# Morpheus_MCU.net
KiCad netlist of a schematic drawn in Altium Designer
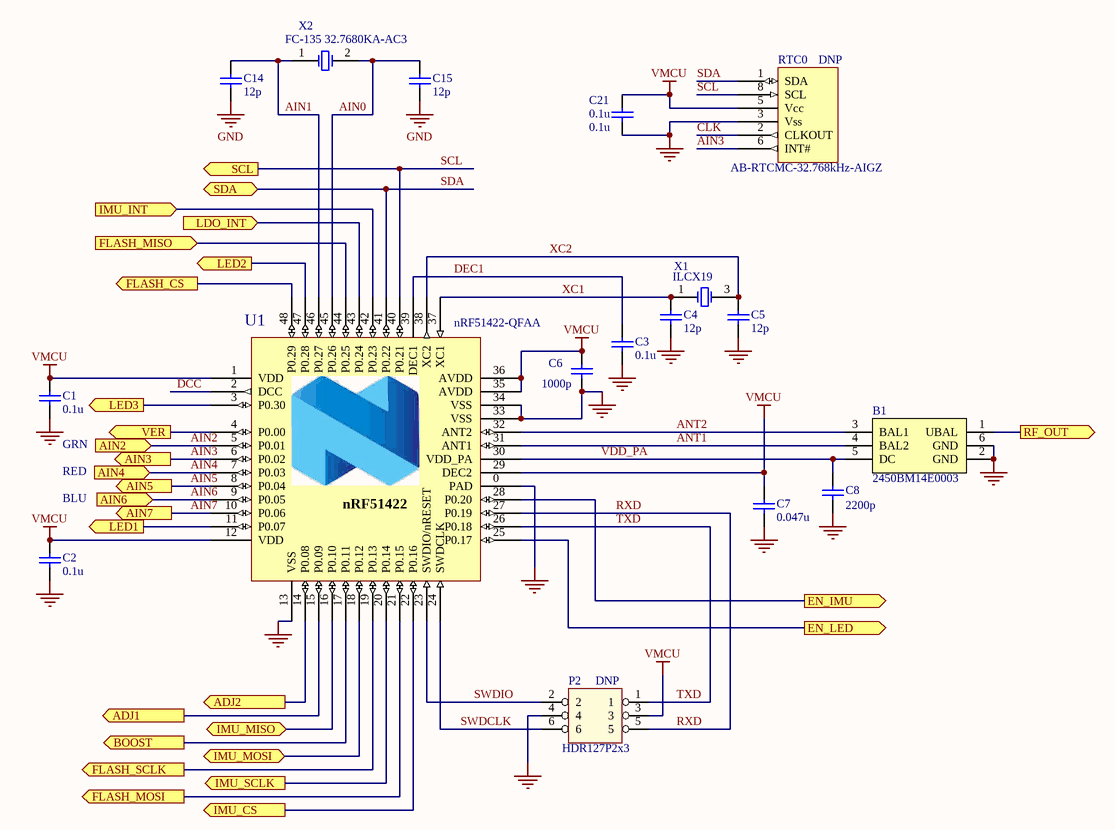
[diagram p0: Morpheus_MCU.SchDoc]

(export (version "E")
  (design (tool "Eeschema 10.0.6"))
  (components
    (comp (ref "B1")
      (value "2450BM14E0003")
      (footprint "DFN50P160X80X70-6N")
      (description "BALUN FILTER for NORDIC nRF51x22 QFN")
      (libsource (lib "Morpheus_pill") (part "2450BM14E0003"))
    )
    (comp (ref "C1")
      (value "0.1u")
      (footprint "CAP0402_SENSE_DVT")
      (description "CAP CER 0.1UF 50V 10% X7R 0402")
      (fields (field (name "TOLERANCE") "10%") (field (name "VOLTAGE") "50V"))
      (libsource (lib "Morpheus_pill") (part "C_0.1u_10_50_X7R_0402"))
    )
    (comp (ref "C2")
      (value "0.1u")
      (footprint "CAP0402_SENSE_DVT")
      (description "CAP CER 0.1UF 50V 10% X7R 0402")
      (fields (field (name "TOLERANCE") "10%") (field (name "VOLTAGE") "50V"))
      (libsource (lib "Morpheus_pill") (part "C_0.1u_10_50_X7R_0402"))
    )
    (comp (ref "C3")
      (value "0.1u")
      (footprint "CAP0402_SENSE_DVT")
      (description "CAP CER 0.1UF 50V 10% X7R 0402")
      (fields (field (name "TOLERANCE") "10%") (field (name "VOLTAGE") "50V"))
      (libsource (lib "Morpheus_pill") (part "C_0.1u_10_50_X7R_0402"))
    )
    (comp (ref "C4")
      (value "12p")
      (footprint "CAP0402_SENSE_DVT")
      (description "CAP CER 12PF 50V 5% NP0 0402")
      (fields (field (name "TOLERANCE") "5%") (field (name "VOLTAGE") "50V"))
      (libsource (lib "Morpheus_pill") (part "C_12p_5_50_C0G_0402"))
    )
    (comp (ref "C5")
      (value "12p")
      (footprint "CAP0402_SENSE_DVT")
      (description "CAP CER 12PF 50V 5% NP0 0402")
      (fields (field (name "TOLERANCE") "5%") (field (name "VOLTAGE") "50V"))
      (libsource (lib "Morpheus_pill") (part "C_12p_5_50_C0G_0402"))
    )
    (comp (ref "C6")
      (value "1000p")
      (footprint "CAP0201_SENSE_DVT")
      (description "CAP CER 1000PF 25V 10% X7R 0201")
      (fields (field (name "TOLERANCE") "10%") (field (name "VOLTAGE") "25V"))
      (libsource (lib "Morpheus_pill") (part "C_1000p_10_25_X7R_0201"))
    )
    (comp (ref "C7")
      (value "0.047u")
      (footprint "CAP0201_SENSE_DVT")
      (description "CAP CER 0.047UF 16V 10% X5R 0201")
      (fields (field (name "TOLERANCE") "10%") (field (name "VOLTAGE") "16V"))
      (libsource (lib "Morpheus_pill") (part "C_0.047u_10_16_X5R_0201"))
    )
    (comp (ref "C8")
      (value "2200p")
      (footprint "CAP0201_SENSE_DVT")
      (description "CAP CER 2200PF 16V 10% X7R 0201")
      (fields (field (name "TOLERANCE") "5 %") (field (name "VOLTAGE") "16V"))
      (libsource (lib "Morpheus_pill") (part "C_2200p_5_16_X7R_0201"))
    )
    (comp (ref "C14")
      (value "12p")
      (footprint "CAP0402_SENSE_DVT")
      (description "CAP CER 12PF 50V 5% NP0 0402")
      (fields (field (name "TOLERANCE") "5%") (field (name "VOLTAGE") "50V"))
      (libsource (lib "Morpheus_pill") (part "C_12p_5_50_C0G_0402"))
    )
    (comp (ref "C15")
      (value "12p")
      (footprint "CAP0402_SENSE_DVT")
      (description "CAP CER 12PF 50V 5% NP0 0402")
      (fields (field (name "TOLERANCE") "5%") (field (name "VOLTAGE") "50V"))
      (libsource (lib "Morpheus_pill") (part "C_12p_5_50_C0G_0402"))
    )
    (comp (ref "C21")
      (value "0.1u")
      (footprint "CAP0402_SENSE_DVT")
      (description "CAP CER 0.1UF 50V 10% X7R 0402")
      (fields
        (field (name "ALTIUM_VALUE") "0.1u")
        (field (name "TOLERANCE") "10%")
        (field (name "VOLTAGE") "50V")
      )
      (libsource (lib "Morpheus_pill") (part "C_0.1u_10_50_X7R_0402"))
    )
    (comp (ref "P2")
      (value "DNP")
      (footprint "HDR1.27-2X3-N")
      (fields (field (name "PN") "HDR127P2x3"))
      (libsource (lib "Morpheus_pill") (part "HDR1.27-2x3-N"))
    )
    (comp (ref "RTC0")
      (value "DNP")
      (footprint "8-CLCC")
      (description "Abracon I2C RTC w/ integrated XO")
      (fields (field (name "PN") "AB-RTCMC-32.768kHz-AIGZ"))
      (libsource (lib "Morpheus_pill") (part "AB-RTCMC-32.768kHz-AIGZ"))
    )
    (comp (ref "U1")
      (value "nRF51422-QFAA")
      (footprint "VQFN40P600X600X100-48")
      (description "Multi-protocol Bluetooth Low Energy, ANT and 2.4GHz proprietary system-on-chip")
      (libsource (lib "Morpheus_pill") (part "nRF51422_QFAA"))
    )
    (comp (ref "X1")
      (value "ILCX19")
      (footprint "ILCX19")
      (description "OSC ILCX19-FB5F18-16.000MHz")
      (libsource (lib "Morpheus_pill") (part "ILCX19"))
    )
    (comp (ref "X2")
      (value "FC-135 32.7680KA-AC3")
      (footprint "Epson_FC-135")
      (description "Crystals 32.768KHz 20ppm 9.0pF")
      (libsource (lib "Morpheus_pill") (part "Espon_FC-135 32.7680KA-AC3"))
    )
  )
  (nets
    (net (code "1") (name "/ADJ1") (class "Default")
      (node (ref "U1") (pin "15") (pinfunction "P0.09_15") (pintype "bidirectional"))
    )
    (net (code "2") (name "/ADJ2") (class "Default")
      (node (ref "U1") (pin "14") (pinfunction "P0.08_14") (pintype "bidirectional"))
    )
    (net (code "3") (name "/AIN0") (class "Default")
      (node (ref "C15") (pin "2") (pinfunction "2_2") (pintype "passive"))
      (node (ref "U1") (pin "45") (pinfunction "P0.26_45") (pintype "bidirectional"))
      (node (ref "X2") (pin "2") (pinfunction "2_2") (pintype "passive"))
    )
    (net (code "4") (name "/AIN1") (class "Default")
      (node (ref "C14") (pin "2") (pinfunction "2_2") (pintype "passive"))
      (node (ref "U1") (pin "46") (pinfunction "P0.27_46") (pintype "bidirectional"))
      (node (ref "X2") (pin "1") (pinfunction "1_1") (pintype "passive"))
    )
    (net (code "5") (name "/AIN2") (class "Default")
      (node (ref "U1") (pin "5") (pinfunction "P0.01_5") (pintype "bidirectional"))
    )
    (net (code "6") (name "/AIN3") (class "Default")
      (node (ref "RTC0") (pin "6") (pinfunction "INT#_6") (pintype "output"))
      (node (ref "U1") (pin "6") (pinfunction "P0.02_6") (pintype "bidirectional"))
    )
    (net (code "7") (name "/AIN4") (class "Default")
      (node (ref "U1") (pin "7") (pinfunction "P0.03_7") (pintype "bidirectional"))
    )
    (net (code "8") (name "/AIN5") (class "Default")
      (node (ref "U1") (pin "8") (pinfunction "P0.04_8") (pintype "bidirectional"))
    )
    (net (code "9") (name "/AIN6") (class "Default")
      (node (ref "U1") (pin "9") (pinfunction "P0.05_9") (pintype "bidirectional"))
    )
    (net (code "10") (name "/AIN7") (class "Default")
      (node (ref "U1") (pin "10") (pinfunction "P0.06_10") (pintype "bidirectional"))
    )
    (net (code "11") (name "/ANT1") (class "Default")
      (node (ref "B1") (pin "4") (pinfunction "BAL2_4") (pintype "passive"))
      (node (ref "U1") (pin "31") (pinfunction "ANT1_31") (pintype "bidirectional"))
    )
    (net (code "12") (name "/ANT2") (class "Default")
      (node (ref "B1") (pin "3") (pinfunction "BAL1_3") (pintype "passive"))
      (node (ref "U1") (pin "32") (pinfunction "ANT2_32") (pintype "bidirectional"))
    )
    (net (code "13") (name "/BOOST") (class "Default")
      (node (ref "U1") (pin "17") (pinfunction "P0.11_17") (pintype "bidirectional"))
    )
    (net (code "14") (name "/CLK") (class "Default")
      (node (ref "RTC0") (pin "2") (pinfunction "CLKOUT_2") (pintype "output"))
    )
    (net (code "15") (name "/DCC") (class "Default")
      (node (ref "U1") (pin "2") (pinfunction "DCC_2") (pintype "output"))
    )
    (net (code "16") (name "/DEC1") (class "Default")
      (node (ref "C3") (pin "2") (pinfunction "2_2") (pintype "passive"))
      (node (ref "U1") (pin "39") (pinfunction "DEC1_39") (pintype "power_in"))
    )
    (net (code "17") (name "/EN_IMU") (class "Default")
      (node (ref "U1") (pin "28") (pinfunction "P0.20_28") (pintype "bidirectional"))
    )
    (net (code "18") (name "/EN_LED") (class "Default")
      (node (ref "U1") (pin "25") (pinfunction "P0.17_25") (pintype "bidirectional"))
    )
    (net (code "19") (name "/FLASH_CS") (class "Default")
      (node (ref "U1") (pin "48") (pinfunction "P0.29_48") (pintype "bidirectional"))
    )
    (net (code "20") (name "/FLASH_MISO") (class "Default")
      (node (ref "U1") (pin "44") (pinfunction "P0.25_44") (pintype "bidirectional"))
    )
    (net (code "21") (name "/FLASH_MOSI") (class "Default")
      (node (ref "U1") (pin "21") (pinfunction "P0.15_21") (pintype "bidirectional"))
    )
    (net (code "22") (name "/FLASH_SCLK") (class "Default")
      (node (ref "U1") (pin "19") (pinfunction "P0.13_19") (pintype "bidirectional"))
    )
    (net (code "23") (name "/IMU_CS") (class "Default")
      (node (ref "U1") (pin "22") (pinfunction "P0.16_22") (pintype "bidirectional"))
    )
    (net (code "24") (name "/IMU_INT") (class "Default")
      (node (ref "U1") (pin "42") (pinfunction "P0.23_42") (pintype "bidirectional"))
    )
    (net (code "25") (name "/IMU_MISO") (class "Default")
      (node (ref "U1") (pin "16") (pinfunction "P0.10_16") (pintype "bidirectional"))
    )
    (net (code "26") (name "/IMU_MOSI") (class "Default")
      (node (ref "U1") (pin "18") (pinfunction "P0.12_18") (pintype "bidirectional"))
    )
    (net (code "27") (name "/IMU_SCLK") (class "Default")
      (node (ref "U1") (pin "20") (pinfunction "P0.14_20") (pintype "bidirectional"))
    )
    (net (code "28") (name "/LDO_INT") (class "Default")
      (node (ref "U1") (pin "43") (pinfunction "P0.24_43") (pintype "bidirectional"))
    )
    (net (code "29") (name "/LED1") (class "Default")
      (node (ref "U1") (pin "11") (pinfunction "P0.07_11") (pintype "bidirectional"))
    )
    (net (code "30") (name "/LED2") (class "Default")
      (node (ref "U1") (pin "47") (pinfunction "P0.28_47") (pintype "bidirectional"))
    )
    (net (code "31") (name "/LED3") (class "Default")
      (node (ref "U1") (pin "3") (pinfunction "P0.30_3") (pintype "bidirectional"))
    )
    (net (code "32") (name "/RF_OUT") (class "Default")
      (node (ref "B1") (pin "1") (pinfunction "UBAL_1") (pintype "passive"))
    )
    (net (code "33") (name "/RXD") (class "Default")
      (node (ref "P2") (pin "5") (pinfunction "5_5") (pintype "passive"))
      (node (ref "U1") (pin "27") (pinfunction "P0.19_27") (pintype "bidirectional"))
    )
    (net (code "34") (name "/SCL") (class "Default")
      (node (ref "RTC0") (pin "8") (pinfunction "SCL_8") (pintype "input"))
      (node (ref "U1") (pin "40") (pinfunction "P0.21_40") (pintype "bidirectional"))
    )
    (net (code "35") (name "/SDA") (class "Default")
      (node (ref "RTC0") (pin "1") (pinfunction "SDA_1") (pintype "bidirectional"))
      (node (ref "U1") (pin "41") (pinfunction "P0.22_41") (pintype "bidirectional"))
    )
    (net (code "36") (name "/SWDCLK") (class "Default")
      (node (ref "P2") (pin "6") (pinfunction "6_6") (pintype "passive"))
      (node (ref "U1") (pin "24") (pinfunction "SWDCLK_24") (pintype "input"))
    )
    (net (code "37") (name "/SWDIO") (class "Default")
      (node (ref "P2") (pin "2") (pinfunction "2_2") (pintype "passive"))
      (node (ref "U1") (pin "23") (pinfunction "SWDIO/nRESET_23") (pintype "input"))
    )
    (net (code "38") (name "/TXD") (class "Default")
      (node (ref "P2") (pin "1") (pinfunction "1_1") (pintype "passive"))
      (node (ref "U1") (pin "26") (pinfunction "P0.18_26") (pintype "bidirectional"))
    )
    (net (code "39") (name "/VDD_PA") (class "Default")
      (node (ref "B1") (pin "5") (pinfunction "DC_5") (pintype "passive"))
      (node (ref "C8") (pin "2") (pinfunction "2_2") (pintype "passive"))
      (node (ref "U1") (pin "30") (pinfunction "VDD_PA_30") (pintype "power_in"))
    )
    (net (code "40") (name "/VER") (class "Default")
      (node (ref "U1") (pin "4") (pinfunction "P0.00_4") (pintype "bidirectional"))
    )
    (net (code "41") (name "/XC1") (class "Default")
      (node (ref "C4") (pin "2") (pinfunction "2_2") (pintype "passive"))
      (node (ref "U1") (pin "37") (pinfunction "XC1_37") (pintype "input"))
      (node (ref "X1") (pin "1") (pinfunction "XTAL1_1") (pintype "passive"))
    )
    (net (code "42") (name "/XC2") (class "Default")
      (node (ref "C5") (pin "2") (pinfunction "2_2") (pintype "passive"))
      (node (ref "U1") (pin "38") (pinfunction "XC2_38") (pintype "output"))
      (node (ref "X1") (pin "3") (pinfunction "XTAL2_3") (pintype "passive"))
    )
    (net (code "43") (name "GND") (class "Default")
      (node (ref "B1") (pin "2") (pinfunction "GND_2") (pintype "passive"))
      (node (ref "B1") (pin "6") (pinfunction "GND_6") (pintype "power_in"))
      (node (ref "C1") (pin "1") (pinfunction "1_1") (pintype "passive"))
      (node (ref "C14") (pin "1") (pinfunction "1_1") (pintype "passive"))
      (node (ref "C15") (pin "1") (pinfunction "1_1") (pintype "passive"))
      (node (ref "C2") (pin "1") (pinfunction "1_1") (pintype "passive"))
      (node (ref "C21") (pin "1") (pinfunction "1_1") (pintype "passive"))
      (node (ref "C3") (pin "1") (pinfunction "1_1") (pintype "passive"))
      (node (ref "C4") (pin "1") (pinfunction "1_1") (pintype "passive"))
      (node (ref "C5") (pin "1") (pinfunction "1_1") (pintype "passive"))
      (node (ref "C6") (pin "1") (pinfunction "1_1") (pintype "passive"))
      (node (ref "C7") (pin "1") (pinfunction "1_1") (pintype "passive"))
      (node (ref "C8") (pin "1") (pinfunction "1_1") (pintype "passive"))
      (node (ref "P2") (pin "4") (pinfunction "4_4") (pintype "passive"))
      (node (ref "RTC0") (pin "3") (pinfunction "Vss_3") (pintype "power_in"))
      (node (ref "U1") (pin "0") (pinfunction "PAD_0") (pintype "power_in"))
      (node (ref "U1") (pin "13") (pinfunction "VSS_13") (pintype "power_in"))
      (node (ref "U1") (pin "33") (pinfunction "VSS_33") (pintype "power_in"))
      (node (ref "U1") (pin "34") (pinfunction "VSS_34") (pintype "power_in"))
    )
    (net (code "44") (name "VMCU") (class "Default")
      (node (ref "C1") (pin "2") (pinfunction "2_2") (pintype "passive"))
      (node (ref "C2") (pin "2") (pinfunction "2_2") (pintype "passive"))
      (node (ref "C21") (pin "2") (pinfunction "2_2") (pintype "passive"))
      (node (ref "C6") (pin "2") (pinfunction "2_2") (pintype "passive"))
      (node (ref "C7") (pin "2") (pinfunction "2_2") (pintype "passive"))
      (node (ref "P2") (pin "3") (pinfunction "3_3") (pintype "passive"))
      (node (ref "RTC0") (pin "5") (pinfunction "Vcc_5") (pintype "power_in"))
      (node (ref "U1") (pin "1") (pinfunction "VDD_1") (pintype "power_in"))
      (node (ref "U1") (pin "12") (pinfunction "VDD_12") (pintype "power_in"))
      (node (ref "U1") (pin "29") (pinfunction "DEC2_29") (pintype "power_in"))
      (node (ref "U1") (pin "35") (pinfunction "AVDD_35") (pintype "power_in"))
      (node (ref "U1") (pin "36") (pinfunction "AVDD_36") (pintype "power_in"))
    )
    (net (code "45") (name "unconnected-(RTC0-NC-Pad4)") (class "Default")
      (node (ref "RTC0") (pin "4") (pinfunction "NC_4") (pintype "passive"))
    )
    (net (code "46") (name "unconnected-(RTC0-NC-Pad7)") (class "Default")
      (node (ref "RTC0") (pin "7") (pinfunction "NC_7") (pintype "passive"))
    )
  )
)
